# Simple-Analog-Amp-BC547.net
KiCad netlist of a schematic drawn in EAGLE
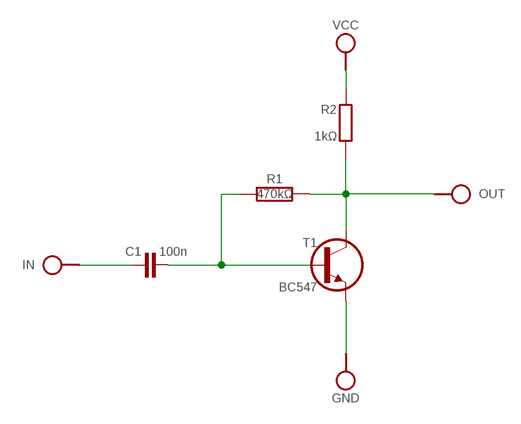
[diagram p0: schematic, sheet 1]

(export (version "E")
  (design (tool "Eeschema 10.0.6"))
  (components
    (comp (ref "C1")
      (value "100n")
      (footprint "eagle-import:C050-020X044")
      (libsource (lib "eagle-import") (part "C-H050-020X044"))
    )
    (comp (ref "GND")
      (value "VPORT")
      (footprint "eagle-import:SPAD")
      (libsource (lib "eagle-import") (part "VPORT"))
    )
    (comp (ref "IN")
      (value "HPORT")
      (footprint "eagle-import:SPAD")
      (libsource (lib "eagle-import") (part "HPORT"))
    )
    (comp (ref "OUT")
      (value "HPORT")
      (footprint "eagle-import:SPAD")
      (libsource (lib "eagle-import") (part "HPORT"))
    )
    (comp (ref "R1")
      (value "470kΩ")
      (footprint "eagle-import:0204_10")
      (libsource (lib "eagle-import") (part "R-H0204/10"))
    )
    (comp (ref "R2")
      (value "1kΩ")
      (footprint "eagle-import:0204_10")
      (libsource (lib "eagle-import") (part "R0204/10"))
    )
    (comp (ref "T1")
      (value "BC547")
      (footprint "eagle-import:TO92-CBE")
      (libsource (lib "eagle-import") (part "BC547"))
    )
    (comp (ref "VCC")
      (value "VPORT")
      (footprint "eagle-import:SPAD")
      (libsource (lib "eagle-import") (part "VPORT"))
    )
  )
  (nets
    (net (code "1") (name "Net-(C1-Pad2)") (class "Default")
      (node (ref "C1") (pin "2") (pinfunction "2_2") (pintype "passive"))
      (node (ref "R1") (pin "1") (pinfunction "1_1") (pintype "passive"))
      (node (ref "T1") (pin "B") (pinfunction "B_B") (pintype "passive"))
    )
    (net (code "2") (name "Net-(GND-P$1)") (class "Default")
      (node (ref "GND") (pin "1") (pinfunction "P$1_1") (pintype "passive"))
      (node (ref "T1") (pin "E") (pinfunction "E_E") (pintype "passive"))
    )
    (net (code "3") (name "Net-(IN-P$1)") (class "Default")
      (node (ref "C1") (pin "1") (pinfunction "1_1") (pintype "passive"))
      (node (ref "IN") (pin "1") (pinfunction "P$1_1") (pintype "passive"))
    )
    (net (code "4") (name "Net-(OUT-P$1)") (class "Default")
      (node (ref "OUT") (pin "1") (pinfunction "P$1_1") (pintype "passive"))
      (node (ref "R1") (pin "2") (pinfunction "2_2") (pintype "passive"))
      (node (ref "R2") (pin "2") (pinfunction "1_2") (pintype "passive"))
      (node (ref "T1") (pin "C") (pinfunction "C_C") (pintype "passive"))
    )
    (net (code "5") (name "Net-(R2-2)") (class "Default")
      (node (ref "R2") (pin "1") (pinfunction "2_1") (pintype "passive"))
      (node (ref "VCC") (pin "1") (pinfunction "P$1_1") (pintype "passive"))
    )
  )
)
